# PS_MIO.net
KiCad netlist of a schematic drawn in Altium Designer
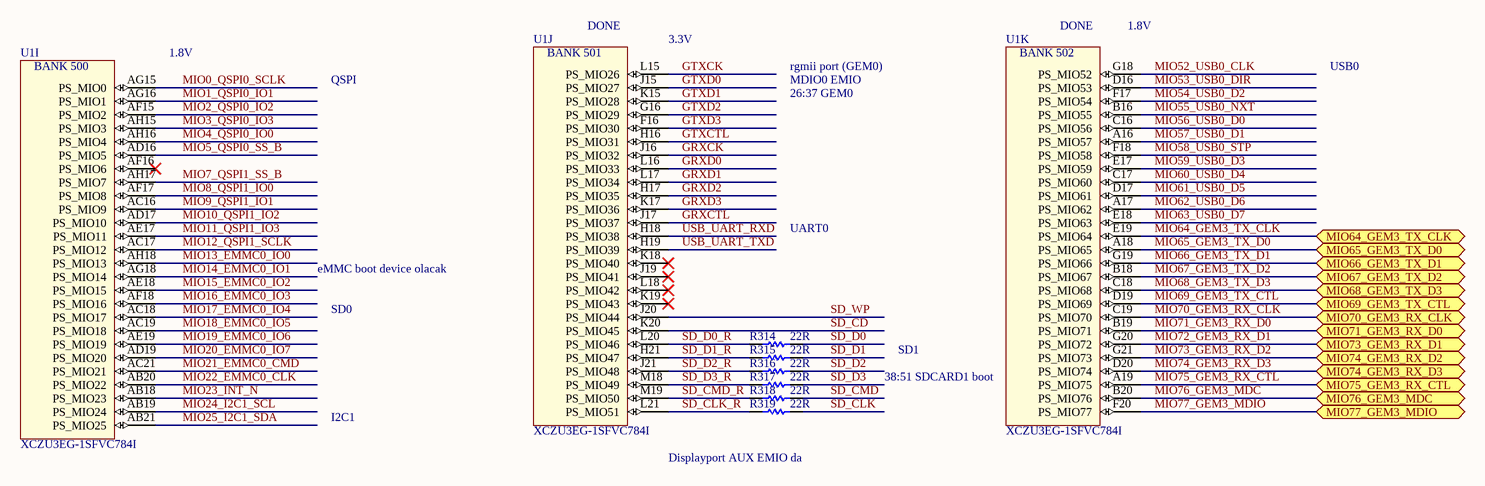
[diagram p0: PS_MIO.SchDoc]

(export (version "E")
  (design (tool "Eeschema 10.0.6"))
  (components
    (comp (ref "R314")
      (value "22R")
      (footprint "RESC1005L_0402")
      (description "RES SMD 22 OHM 1% 1/10W 0402")
      (fields (field (name "POWER") "1/10W") (field (name "TOLERANCE") "1%"))
      (libsource (lib "Ultrascale_SchLib") (part "RES0402_22R_0W1_1T"))
    )
    (comp (ref "R315")
      (value "22R")
      (footprint "RESC1005L_0402")
      (description "RES SMD 22 OHM 1% 1/10W 0402")
      (fields (field (name "POWER") "1/10W") (field (name "TOLERANCE") "1%"))
      (libsource (lib "Ultrascale_SchLib") (part "RES0402_22R_0W1_1T"))
    )
    (comp (ref "R316")
      (value "22R")
      (footprint "RESC1005L_0402")
      (description "RES SMD 22 OHM 1% 1/10W 0402")
      (fields (field (name "POWER") "1/10W") (field (name "TOLERANCE") "1%"))
      (libsource (lib "Ultrascale_SchLib") (part "RES0402_22R_0W1_1T"))
    )
    (comp (ref "R317")
      (value "22R")
      (footprint "RESC1005L_0402")
      (description "RES SMD 22 OHM 1% 1/10W 0402")
      (fields (field (name "POWER") "1/10W") (field (name "TOLERANCE") "1%"))
      (libsource (lib "Ultrascale_SchLib") (part "RES0402_22R_0W1_1T"))
    )
    (comp (ref "R318")
      (value "22R")
      (footprint "RESC1005L_0402")
      (description "RES SMD 22 OHM 1% 1/10W 0402")
      (fields (field (name "POWER") "1/10W") (field (name "TOLERANCE") "1%"))
      (libsource (lib "Ultrascale_SchLib") (part "RES0402_22R_0W1_1T"))
    )
    (comp (ref "R319")
      (value "22R")
      (footprint "RESC1005L_0402")
      (description "RES SMD 22 OHM 1% 1/10W 0402")
      (fields (field (name "POWER") "1/10W") (field (name "TOLERANCE") "1%"))
      (libsource (lib "Ultrascale_SchLib") (part "RES0402_22R_0W1_1T"))
    )
    (comp (ref "U1")
      (value "XCZU3EG-1SFVC784I")
      (footprint "BGA784x28")
      (description "IC FPGA 252 I/O 784FCBGA - XILINX ZYNQ ULTRASCALE+")
      (libsource (lib "Ultrascale_SchLib") (part "XCZU3EG-1SFVC784I"))
    )
  )
  (nets
    (net (code "1") (name "/GRXCK") (class "Default")
      (node (ref "U1") (pin "J16") (pinfunction "PS_MIO32_J16") (pintype "bidirectional"))
    )
    (net (code "2") (name "/GRXCTL") (class "Default")
      (node (ref "U1") (pin "J17") (pinfunction "PS_MIO37_J17") (pintype "bidirectional"))
    )
    (net (code "3") (name "/GRXD0") (class "Default")
      (node (ref "U1") (pin "L16") (pinfunction "PS_MIO33_L16") (pintype "bidirectional"))
    )
    (net (code "4") (name "/GRXD1") (class "Default")
      (node (ref "U1") (pin "L17") (pinfunction "PS_MIO34_L17") (pintype "bidirectional"))
    )
    (net (code "5") (name "/GRXD2") (class "Default")
      (node (ref "U1") (pin "H17") (pinfunction "PS_MIO35_H17") (pintype "bidirectional"))
    )
    (net (code "6") (name "/GRXD3") (class "Default")
      (node (ref "U1") (pin "K17") (pinfunction "PS_MIO36_K17") (pintype "bidirectional"))
    )
    (net (code "7") (name "/GTXCK") (class "Default")
      (node (ref "U1") (pin "L15") (pinfunction "PS_MIO26_L15") (pintype "bidirectional"))
    )
    (net (code "8") (name "/GTXCTL") (class "Default")
      (node (ref "U1") (pin "H16") (pinfunction "PS_MIO31_H16") (pintype "bidirectional"))
    )
    (net (code "9") (name "/GTXD0") (class "Default")
      (node (ref "U1") (pin "J15") (pinfunction "PS_MIO27_J15") (pintype "bidirectional"))
    )
    (net (code "10") (name "/GTXD1") (class "Default")
      (node (ref "U1") (pin "K15") (pinfunction "PS_MIO28_K15") (pintype "bidirectional"))
    )
    (net (code "11") (name "/GTXD2") (class "Default")
      (node (ref "U1") (pin "G16") (pinfunction "PS_MIO29_G16") (pintype "bidirectional"))
    )
    (net (code "12") (name "/GTXD3") (class "Default")
      (node (ref "U1") (pin "F16") (pinfunction "PS_MIO30_F16") (pintype "bidirectional"))
    )
    (net (code "13") (name "/MIO0_QSPI0_SCLK") (class "Default")
      (node (ref "U1") (pin "AG15") (pinfunction "PS_MIO0_AG15") (pintype "bidirectional"))
    )
    (net (code "14") (name "/MIO1_QSPI0_IO1") (class "Default")
      (node (ref "U1") (pin "AG16") (pinfunction "PS_MIO1_AG16") (pintype "bidirectional"))
    )
    (net (code "15") (name "/MIO2_QSPI0_IO2") (class "Default")
      (node (ref "U1") (pin "AF15") (pinfunction "PS_MIO2_AF15") (pintype "bidirectional"))
    )
    (net (code "16") (name "/MIO3_QSPI0_IO3") (class "Default")
      (node (ref "U1") (pin "AH15") (pinfunction "PS_MIO3_AH15") (pintype "bidirectional"))
    )
    (net (code "17") (name "/MIO4_QSPI0_IO0") (class "Default")
      (node (ref "U1") (pin "AH16") (pinfunction "PS_MIO4_AH16") (pintype "bidirectional"))
    )
    (net (code "18") (name "/MIO5_QSPI0_SS_B") (class "Default")
      (node (ref "U1") (pin "AD16") (pinfunction "PS_MIO5_AD16") (pintype "bidirectional"))
    )
    (net (code "19") (name "/MIO7_QSPI1_SS_B") (class "Default")
      (node (ref "U1") (pin "AH17") (pinfunction "PS_MIO7_AH17") (pintype "bidirectional"))
    )
    (net (code "20") (name "/MIO8_QSPI1_IO0") (class "Default")
      (node (ref "U1") (pin "AF17") (pinfunction "PS_MIO8_AF17") (pintype "bidirectional"))
    )
    (net (code "21") (name "/MIO9_QSPI1_IO1") (class "Default")
      (node (ref "U1") (pin "AC16") (pinfunction "PS_MIO9_AC16") (pintype "bidirectional"))
    )
    (net (code "22") (name "/MIO10_QSPI1_IO2") (class "Default")
      (node (ref "U1") (pin "AD17") (pinfunction "PS_MIO10_AD17") (pintype "bidirectional"))
    )
    (net (code "23") (name "/MIO11_QSPI1_IO3") (class "Default")
      (node (ref "U1") (pin "AE17") (pinfunction "PS_MIO11_AE17") (pintype "bidirectional"))
    )
    (net (code "24") (name "/MIO12_QSPI1_SCLK") (class "Default")
      (node (ref "U1") (pin "AC17") (pinfunction "PS_MIO12_AC17") (pintype "bidirectional"))
    )
    (net (code "25") (name "/MIO13_EMMC0_IO0") (class "Default")
      (node (ref "U1") (pin "AH18") (pinfunction "PS_MIO13_AH18") (pintype "bidirectional"))
    )
    (net (code "26") (name "/MIO14_EMMC0_IO1") (class "Default")
      (node (ref "U1") (pin "AG18") (pinfunction "PS_MIO14_AG18") (pintype "bidirectional"))
    )
    (net (code "27") (name "/MIO15_EMMC0_IO2") (class "Default")
      (node (ref "U1") (pin "AE18") (pinfunction "PS_MIO15_AE18") (pintype "bidirectional"))
    )
    (net (code "28") (name "/MIO16_EMMC0_IO3") (class "Default")
      (node (ref "U1") (pin "AF18") (pinfunction "PS_MIO16_AF18") (pintype "bidirectional"))
    )
    (net (code "29") (name "/MIO17_EMMC0_IO4") (class "Default")
      (node (ref "U1") (pin "AC18") (pinfunction "PS_MIO17_AC18") (pintype "bidirectional"))
    )
    (net (code "30") (name "/MIO18_EMMC0_IO5") (class "Default")
      (node (ref "U1") (pin "AC19") (pinfunction "PS_MIO18_AC19") (pintype "bidirectional"))
    )
    (net (code "31") (name "/MIO19_EMMC0_IO6") (class "Default")
      (node (ref "U1") (pin "AE19") (pinfunction "PS_MIO19_AE19") (pintype "bidirectional"))
    )
    (net (code "32") (name "/MIO20_EMMC0_IO7") (class "Default")
      (node (ref "U1") (pin "AD19") (pinfunction "PS_MIO20_AD19") (pintype "bidirectional"))
    )
    (net (code "33") (name "/MIO21_EMMC0_CMD") (class "Default")
      (node (ref "U1") (pin "AC21") (pinfunction "PS_MIO21_AC21") (pintype "bidirectional"))
    )
    (net (code "34") (name "/MIO22_EMMC0_CLK") (class "Default")
      (node (ref "U1") (pin "AB20") (pinfunction "PS_MIO22_AB20") (pintype "bidirectional"))
    )
    (net (code "35") (name "/MIO23_INT_N") (class "Default")
      (node (ref "U1") (pin "AB18") (pinfunction "PS_MIO23_AB18") (pintype "bidirectional"))
    )
    (net (code "36") (name "/MIO24_I2C1_SCL") (class "Default")
      (node (ref "U1") (pin "AB19") (pinfunction "PS_MIO24_AB19") (pintype "bidirectional"))
    )
    (net (code "37") (name "/MIO25_I2C1_SDA") (class "Default")
      (node (ref "U1") (pin "AB21") (pinfunction "PS_MIO25_AB21") (pintype "bidirectional"))
    )
    (net (code "38") (name "/MIO52_USB0_CLK") (class "Default")
      (node (ref "U1") (pin "G18") (pinfunction "PS_MIO52_G18") (pintype "bidirectional"))
    )
    (net (code "39") (name "/MIO53_USB0_DIR") (class "Default")
      (node (ref "U1") (pin "D16") (pinfunction "PS_MIO53_D16") (pintype "bidirectional"))
    )
    (net (code "40") (name "/MIO54_USB0_D2") (class "Default")
      (node (ref "U1") (pin "F17") (pinfunction "PS_MIO54_F17") (pintype "bidirectional"))
    )
    (net (code "41") (name "/MIO55_USB0_NXT") (class "Default")
      (node (ref "U1") (pin "B16") (pinfunction "PS_MIO55_B16") (pintype "bidirectional"))
    )
    (net (code "42") (name "/MIO56_USB0_D0") (class "Default")
      (node (ref "U1") (pin "C16") (pinfunction "PS_MIO56_C16") (pintype "bidirectional"))
    )
    (net (code "43") (name "/MIO57_USB0_D1") (class "Default")
      (node (ref "U1") (pin "A16") (pinfunction "PS_MIO57_A16") (pintype "bidirectional"))
    )
    (net (code "44") (name "/MIO58_USB0_STP") (class "Default")
      (node (ref "U1") (pin "F18") (pinfunction "PS_MIO58_F18") (pintype "bidirectional"))
    )
    (net (code "45") (name "/MIO59_USB0_D3") (class "Default")
      (node (ref "U1") (pin "E17") (pinfunction "PS_MIO59_E17") (pintype "bidirectional"))
    )
    (net (code "46") (name "/MIO60_USB0_D4") (class "Default")
      (node (ref "U1") (pin "C17") (pinfunction "PS_MIO60_C17") (pintype "bidirectional"))
    )
    (net (code "47") (name "/MIO61_USB0_D5") (class "Default")
      (node (ref "U1") (pin "D17") (pinfunction "PS_MIO61_D17") (pintype "bidirectional"))
    )
    (net (code "48") (name "/MIO62_USB0_D6") (class "Default")
      (node (ref "U1") (pin "A17") (pinfunction "PS_MIO62_A17") (pintype "bidirectional"))
    )
    (net (code "49") (name "/MIO63_USB0_D7") (class "Default")
      (node (ref "U1") (pin "E18") (pinfunction "PS_MIO63_E18") (pintype "bidirectional"))
    )
    (net (code "50") (name "/MIO64_GEM3_TX_CLK") (class "Default")
      (node (ref "U1") (pin "E19") (pinfunction "PS_MIO64_E19") (pintype "bidirectional"))
    )
    (net (code "51") (name "/MIO65_GEM3_TX_D0") (class "Default")
      (node (ref "U1") (pin "A18") (pinfunction "PS_MIO65_A18") (pintype "bidirectional"))
    )
    (net (code "52") (name "/MIO66_GEM3_TX_D1") (class "Default")
      (node (ref "U1") (pin "G19") (pinfunction "PS_MIO66_G19") (pintype "bidirectional"))
    )
    (net (code "53") (name "/MIO67_GEM3_TX_D2") (class "Default")
      (node (ref "U1") (pin "B18") (pinfunction "PS_MIO67_B18") (pintype "bidirectional"))
    )
    (net (code "54") (name "/MIO68_GEM3_TX_D3") (class "Default")
      (node (ref "U1") (pin "C18") (pinfunction "PS_MIO68_C18") (pintype "bidirectional"))
    )
    (net (code "55") (name "/MIO69_GEM3_TX_CTL") (class "Default")
      (node (ref "U1") (pin "D19") (pinfunction "PS_MIO69_D19") (pintype "bidirectional"))
    )
    (net (code "56") (name "/MIO70_GEM3_RX_CLK") (class "Default")
      (node (ref "U1") (pin "C19") (pinfunction "PS_MIO70_C19") (pintype "bidirectional"))
    )
    (net (code "57") (name "/MIO71_GEM3_RX_D0") (class "Default")
      (node (ref "U1") (pin "B19") (pinfunction "PS_MIO71_B19") (pintype "bidirectional"))
    )
    (net (code "58") (name "/MIO72_GEM3_RX_D1") (class "Default")
      (node (ref "U1") (pin "G20") (pinfunction "PS_MIO72_G20") (pintype "bidirectional"))
    )
    (net (code "59") (name "/MIO73_GEM3_RX_D2") (class "Default")
      (node (ref "U1") (pin "G21") (pinfunction "PS_MIO73_G21") (pintype "bidirectional"))
    )
    (net (code "60") (name "/MIO74_GEM3_RX_D3") (class "Default")
      (node (ref "U1") (pin "D20") (pinfunction "PS_MIO74_D20") (pintype "bidirectional"))
    )
    (net (code "61") (name "/MIO75_GEM3_RX_CTL") (class "Default")
      (node (ref "U1") (pin "A19") (pinfunction "PS_MIO75_A19") (pintype "bidirectional"))
    )
    (net (code "62") (name "/MIO76_GEM3_MDC") (class "Default")
      (node (ref "U1") (pin "B20") (pinfunction "PS_MIO76_B20") (pintype "bidirectional"))
    )
    (net (code "63") (name "/MIO77_GEM3_MDIO") (class "Default")
      (node (ref "U1") (pin "F20") (pinfunction "PS_MIO77_F20") (pintype "bidirectional"))
    )
    (net (code "64") (name "/SD_CD") (class "Default")
      (node (ref "U1") (pin "K20") (pinfunction "PS_MIO45_K20") (pintype "bidirectional"))
    )
    (net (code "65") (name "/SD_CLK") (class "Default")
      (node (ref "R319") (pin "2") (pinfunction "2_2") (pintype "passive"))
    )
    (net (code "66") (name "/SD_CLK_R") (class "Default")
      (node (ref "R319") (pin "1") (pinfunction "1_1") (pintype "passive"))
      (node (ref "U1") (pin "L21") (pinfunction "PS_MIO51_L21") (pintype "bidirectional"))
    )
    (net (code "67") (name "/SD_CMD") (class "Default")
      (node (ref "R318") (pin "2") (pinfunction "2_2") (pintype "passive"))
    )
    (net (code "68") (name "/SD_CMD_R") (class "Default")
      (node (ref "R318") (pin "1") (pinfunction "1_1") (pintype "passive"))
      (node (ref "U1") (pin "M19") (pinfunction "PS_MIO50_M19") (pintype "bidirectional"))
    )
    (net (code "69") (name "/SD_D0") (class "Default")
      (node (ref "R314") (pin "2") (pinfunction "2_2") (pintype "passive"))
    )
    (net (code "70") (name "/SD_D0_R") (class "Default")
      (node (ref "R314") (pin "1") (pinfunction "1_1") (pintype "passive"))
      (node (ref "U1") (pin "L20") (pinfunction "PS_MIO46_L20") (pintype "bidirectional"))
    )
    (net (code "71") (name "/SD_D1") (class "Default")
      (node (ref "R315") (pin "2") (pinfunction "2_2") (pintype "passive"))
    )
    (net (code "72") (name "/SD_D1_R") (class "Default")
      (node (ref "R315") (pin "1") (pinfunction "1_1") (pintype "passive"))
      (node (ref "U1") (pin "H21") (pinfunction "PS_MIO47_H21") (pintype "bidirectional"))
    )
    (net (code "73") (name "/SD_D2") (class "Default")
      (node (ref "R316") (pin "2") (pinfunction "2_2") (pintype "passive"))
    )
    (net (code "74") (name "/SD_D2_R") (class "Default")
      (node (ref "R316") (pin "1") (pinfunction "1_1") (pintype "passive"))
      (node (ref "U1") (pin "J21") (pinfunction "PS_MIO48_J21") (pintype "bidirectional"))
    )
    (net (code "75") (name "/SD_D3") (class "Default")
      (node (ref "R317") (pin "2") (pinfunction "2_2") (pintype "passive"))
    )
    (net (code "76") (name "/SD_D3_R") (class "Default")
      (node (ref "R317") (pin "1") (pinfunction "1_1") (pintype "passive"))
      (node (ref "U1") (pin "M18") (pinfunction "PS_MIO49_M18") (pintype "bidirectional"))
    )
    (net (code "77") (name "/SD_WP") (class "Default")
      (node (ref "U1") (pin "J20") (pinfunction "PS_MIO44_J20") (pintype "bidirectional"))
    )
    (net (code "78") (name "/USB_UART_RXD") (class "Default")
      (node (ref "U1") (pin "H18") (pinfunction "PS_MIO38_H18") (pintype "bidirectional"))
    )
    (net (code "79") (name "/USB_UART_TXD") (class "Default")
      (node (ref "U1") (pin "H19") (pinfunction "PS_MIO39_H19") (pintype "bidirectional"))
    )
    (net (code "80") (name "unconnected-(U1I-PS_MIO6-PadAF16)") (class "Default")
      (node (ref "U1") (pin "AF16") (pinfunction "PS_MIO6_AF16") (pintype "bidirectional+no_connect"))
    )
    (net (code "81") (name "unconnected-(U1J-PS_MIO40-PadK18)") (class "Default")
      (node (ref "U1") (pin "K18") (pinfunction "PS_MIO40_K18") (pintype "bidirectional+no_connect"))
    )
    (net (code "82") (name "unconnected-(U1J-PS_MIO41-PadJ19)") (class "Default")
      (node (ref "U1") (pin "J19") (pinfunction "PS_MIO41_J19") (pintype "bidirectional+no_connect"))
    )
    (net (code "83") (name "unconnected-(U1J-PS_MIO42-PadL18)") (class "Default")
      (node (ref "U1") (pin "L18") (pinfunction "PS_MIO42_L18") (pintype "bidirectional+no_connect"))
    )
    (net (code "84") (name "unconnected-(U1J-PS_MIO43-PadK19)") (class "Default")
      (node (ref "U1") (pin "K19") (pinfunction "PS_MIO43_K19") (pintype "bidirectional+no_connect"))
    )
  )
)
